# Adafruit_CCS811_STEMMA_QT.net
KiCad netlist of a schematic drawn in EAGLE
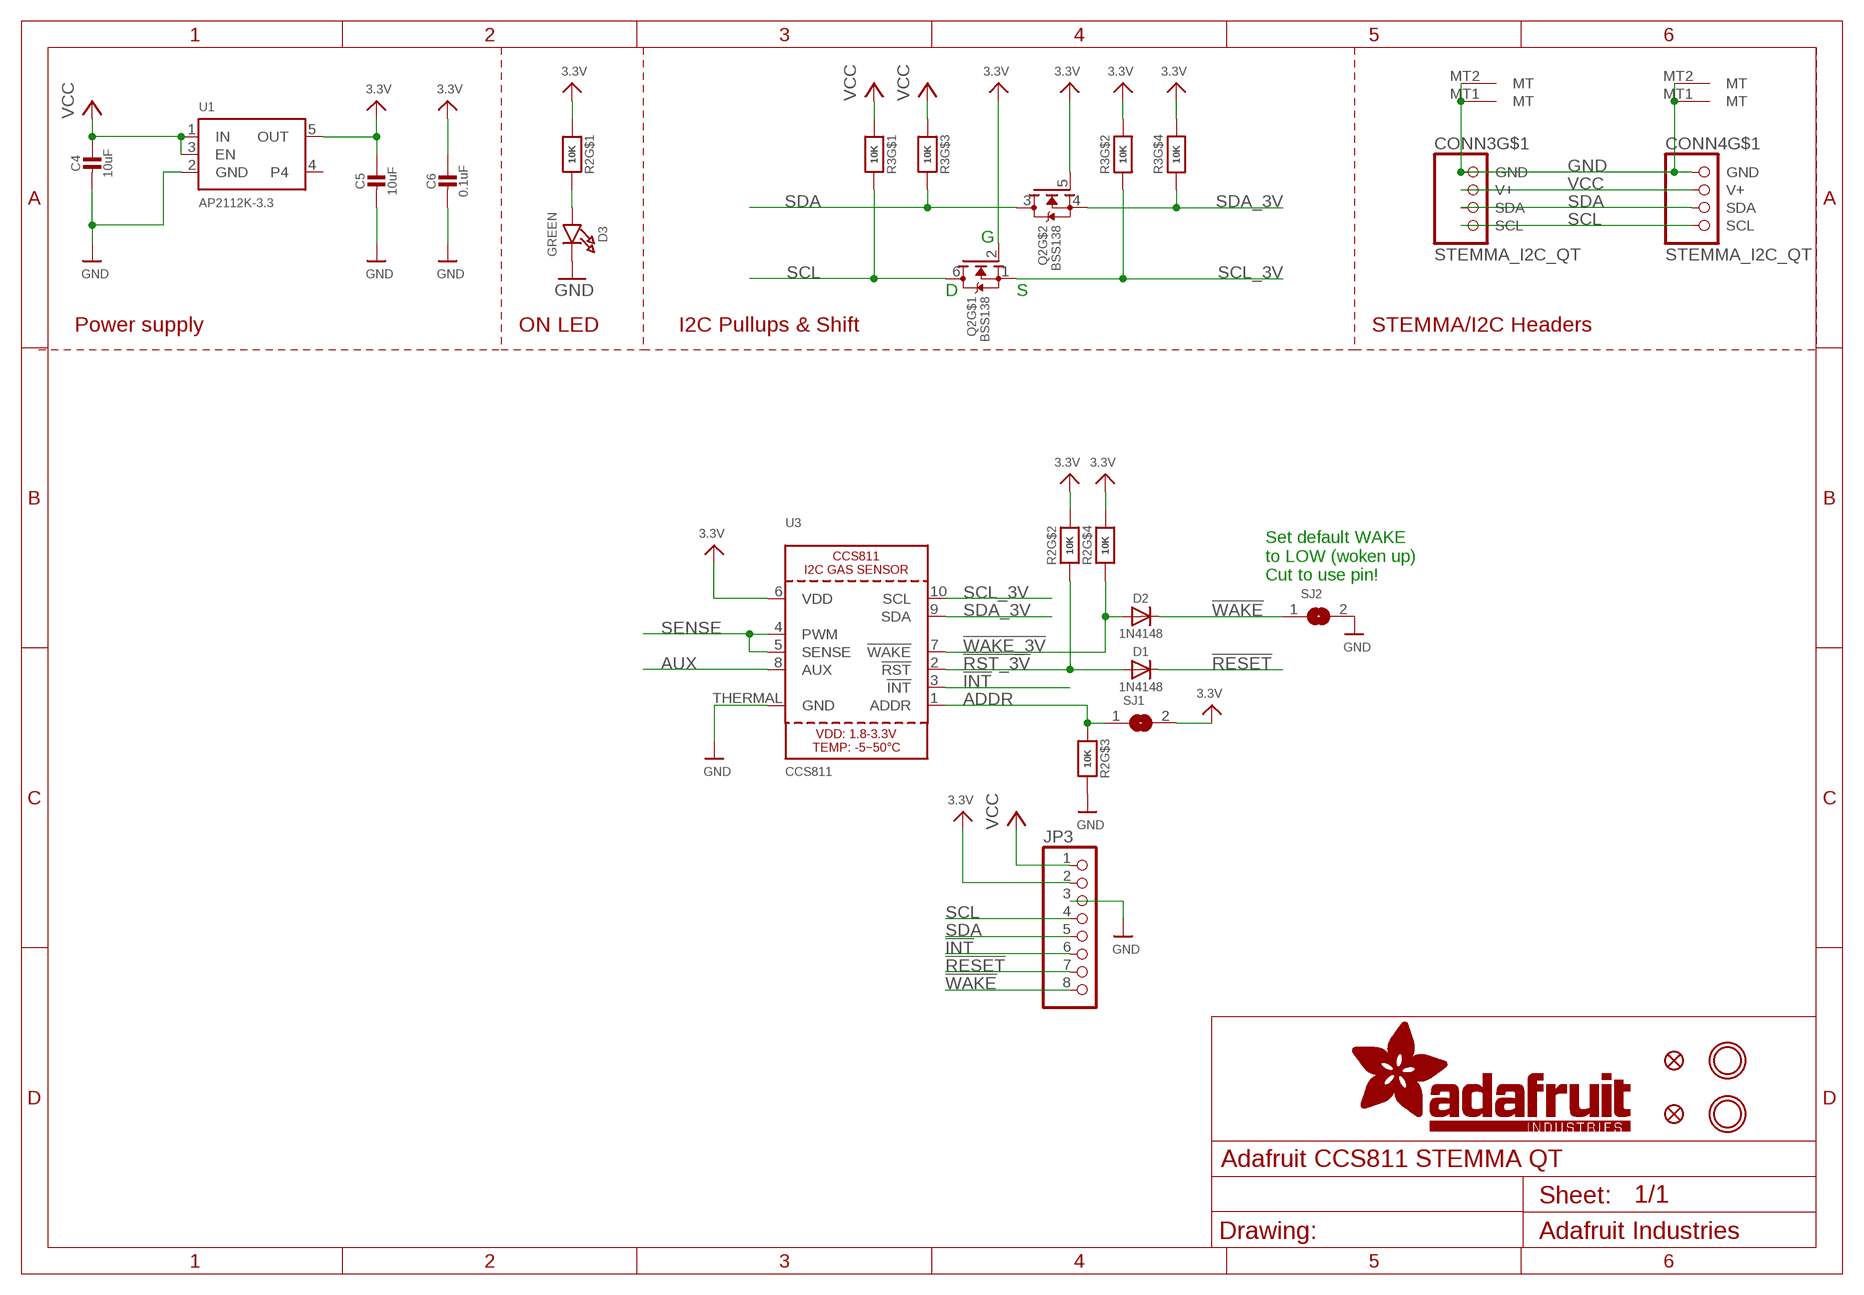
[diagram p0: schematic, sheet 1]

(export (version "E")
  (design (tool "Eeschema 10.0.6"))
  (components
    (comp (ref "C4")
      (value "10uF")
      (footprint "eagle-import:0805-NO")
      (libsource (lib "eagle-import") (part "CAP_CERAMIC0805-NOOUTLINE"))
    )
    (comp (ref "C5")
      (value "10uF")
      (footprint "eagle-import:0805-NO")
      (libsource (lib "eagle-import") (part "CAP_CERAMIC0805-NOOUTLINE"))
    )
    (comp (ref "C6")
      (value "0.1uF")
      (footprint "eagle-import:0603-NO")
      (libsource (lib "eagle-import") (part "CAP_CERAMIC0603_NO"))
    )
    (comp (ref "CONN3")
      (value "STEMMA_I2C_QT")
      (footprint "eagle-import:JST_SH4")
      (libsource (lib "eagle-import") (part "STEMMA_I2C_QT"))
    )
    (comp (ref "CONN4")
      (value "STEMMA_I2C_QT")
      (footprint "eagle-import:JST_SH4")
      (libsource (lib "eagle-import") (part "STEMMA_I2C_QT"))
    )
    (comp (ref "D1")
      (value "1N4148")
      (footprint "eagle-import:SOD-323")
      (libsource (lib "eagle-import") (part "DIODESOD-323"))
    )
    (comp (ref "D2")
      (value "1N4148")
      (footprint "eagle-import:SOD-323")
      (libsource (lib "eagle-import") (part "DIODESOD-323"))
    )
    (comp (ref "D3")
      (value "GREEN")
      (footprint "eagle-import:CHIPLED_0603_NOOUTLINE")
      (libsource (lib "eagle-import") (part "LED0603_NOOUTLINE"))
    )
    (comp (ref "FID3")
      (value "FIDUCIAL_1MM")
      (footprint "eagle-import:FIDUCIAL_1MM")
      (libsource (lib "eagle-import") (part "FIDUCIAL_1MM"))
    )
    (comp (ref "FID4")
      (value "FIDUCIAL_1MM")
      (footprint "eagle-import:FIDUCIAL_1MM")
      (libsource (lib "eagle-import") (part "FIDUCIAL_1MM"))
    )
    (comp (ref "JP3")
      (value "HEADER-1X870MIL")
      (footprint "eagle-import:1X08_ROUND_70")
      (libsource (lib "eagle-import") (part "HEADER-1X870MIL"))
    )
    (comp (ref "Q2")
      (value "BSS138")
      (footprint "eagle-import:SOT363")
      (libsource (lib "eagle-import") (part "MOSFET-N_DUAL"))
    )
    (comp (ref "R2")
      (value "10K")
      (footprint "eagle-import:RESPACK_4X0603")
      (libsource (lib "eagle-import") (part "RESISTOR_4PACK"))
    )
    (comp (ref "R3")
      (value "10K")
      (footprint "eagle-import:RESPACK_4X0603")
      (libsource (lib "eagle-import") (part "RESISTOR_4PACK"))
    )
    (comp (ref "SJ1")
      (value "SOLDERJUMPER")
      (footprint "eagle-import:SOLDERJUMPER_ARROW_NOPASTE")
      (libsource (lib "eagle-import") (part "SOLDERJUMPER"))
    )
    (comp (ref "SJ2")
      (value "SOLDERJUMPERCLOSED")
      (footprint "eagle-import:SOLDERJUMPER_CLOSEDWIRE")
      (libsource (lib "eagle-import") (part "SOLDERJUMPERCLOSED"))
    )
    (comp (ref "U$39")
      (value "MOUNTINGHOLE2.5")
      (footprint "eagle-import:MOUNTINGHOLE_2.5_PLATED")
      (libsource (lib "eagle-import") (part "MOUNTINGHOLE2.5"))
    )
    (comp (ref "U$40")
      (value "MOUNTINGHOLE2.5")
      (footprint "eagle-import:MOUNTINGHOLE_2.5_PLATED")
      (libsource (lib "eagle-import") (part "MOUNTINGHOLE2.5"))
    )
    (comp (ref "U1")
      (value "AP2112K-3.3")
      (footprint "eagle-import:SOT23-5")
      (libsource (lib "eagle-import") (part "VREG_SOT23-5"))
    )
    (comp (ref "U3")
      (value "CCS811")
      (footprint "eagle-import:CCS811")
      (libsource (lib "eagle-import") (part "CCS811"))
    )
  )
  (nets
    (net (code "1") (name "/ADDR") (class "Default")
      (node (ref "R2") (pin "3") (pinfunction "1_3") (pintype "passive"))
      (node (ref "SJ1") (pin "1") (pinfunction "1_1") (pintype "passive"))
      (node (ref "U3") (pin "1") (pinfunction "ADDR_1") (pintype "input"))
    )
    (net (code "2") (name "/AUX") (class "Default")
      (node (ref "U3") (pin "8") (pinfunction "AUX_8") (pintype "passive"))
    )
    (net (code "3") (name "/SCL") (class "Default")
      (node (ref "CONN3") (pin "4") (pinfunction "SCL_4") (pintype "passive"))
      (node (ref "CONN4") (pin "4") (pinfunction "SCL_4") (pintype "passive"))
      (node (ref "JP3") (pin "4") (pinfunction "4_4") (pintype "passive"))
      (node (ref "Q2") (pin "6") (pinfunction "D_6") (pintype "bidirectional"))
      (node (ref "R3") (pin "8") (pinfunction "2_8") (pintype "passive"))
    )
    (net (code "4") (name "/SCL_3V") (class "Default")
      (node (ref "Q2") (pin "1") (pinfunction "S_1") (pintype "bidirectional"))
      (node (ref "R3") (pin "7") (pinfunction "2_7") (pintype "passive"))
      (node (ref "U3") (pin "10") (pinfunction "SCL_10") (pintype "bidirectional"))
    )
    (net (code "5") (name "/SDA") (class "Default")
      (node (ref "CONN3") (pin "3") (pinfunction "SDA_3") (pintype "passive"))
      (node (ref "CONN4") (pin "3") (pinfunction "SDA_3") (pintype "passive"))
      (node (ref "JP3") (pin "5") (pinfunction "5_5") (pintype "passive"))
      (node (ref "Q2") (pin "3") (pinfunction "D_3") (pintype "bidirectional"))
      (node (ref "R3") (pin "6") (pinfunction "2_6") (pintype "passive"))
    )
    (net (code "6") (name "/SDA_3V") (class "Default")
      (node (ref "Q2") (pin "4") (pinfunction "S_4") (pintype "bidirectional"))
      (node (ref "R3") (pin "5") (pinfunction "2_5") (pintype "passive"))
      (node (ref "U3") (pin "9") (pinfunction "SDA_9") (pintype "bidirectional"))
    )
    (net (code "7") (name "/SENSE") (class "Default")
      (node (ref "U3") (pin "4") (pinfunction "PWM_4") (pintype "output"))
      (node (ref "U3") (pin "5") (pinfunction "SENSE_5") (pintype "input"))
    )
    (net (code "8") (name "/~{INT}") (class "Default")
      (node (ref "JP3") (pin "6") (pinfunction "6_6") (pintype "passive"))
      (node (ref "U3") (pin "3") (pinfunction "~{INT}_3") (pintype "output"))
    )
    (net (code "9") (name "/~{RESET}") (class "Default")
      (node (ref "D1") (pin "C") (pinfunction "C_C") (pintype "passive"))
      (node (ref "JP3") (pin "7") (pinfunction "7_7") (pintype "passive"))
    )
    (net (code "10") (name "/~{RST_3V}") (class "Default")
      (node (ref "D1") (pin "A") (pinfunction "A_A") (pintype "passive"))
      (node (ref "R2") (pin "2") (pinfunction "1_2") (pintype "passive"))
      (node (ref "U3") (pin "2") (pinfunction "~{RST}_2") (pintype "input"))
    )
    (net (code "11") (name "/~{WAKE_3V}") (class "Default")
      (node (ref "D2") (pin "A") (pinfunction "A_A") (pintype "passive"))
      (node (ref "R2") (pin "4") (pinfunction "1_4") (pintype "passive"))
      (node (ref "U3") (pin "7") (pinfunction "~{WAKE}_7") (pintype "input"))
    )
    (net (code "12") (name "/~{WAKE}") (class "Default")
      (node (ref "D2") (pin "C") (pinfunction "C_C") (pintype "passive"))
      (node (ref "JP3") (pin "8") (pinfunction "8_8") (pintype "passive"))
      (node (ref "SJ2") (pin "1") (pinfunction "1_1") (pintype "passive"))
    )
    (net (code "13") (name "3.3V") (class "Default")
      (node (ref "C5") (pin "1") (pinfunction "1_1") (pintype "passive"))
      (node (ref "C6") (pin "1") (pinfunction "1_1") (pintype "passive"))
      (node (ref "JP3") (pin "2") (pinfunction "2_2") (pintype "passive"))
      (node (ref "Q2") (pin "2") (pinfunction "G_2") (pintype "bidirectional"))
      (node (ref "Q2") (pin "5") (pinfunction "G_5") (pintype "bidirectional"))
      (node (ref "R2") (pin "1") (pinfunction "1_1") (pintype "passive"))
      (node (ref "R2") (pin "5") (pinfunction "2_5") (pintype "passive"))
      (node (ref "R2") (pin "7") (pinfunction "2_7") (pintype "passive"))
      (node (ref "R3") (pin "2") (pinfunction "1_2") (pintype "passive"))
      (node (ref "R3") (pin "4") (pinfunction "1_4") (pintype "passive"))
      (node (ref "SJ1") (pin "2") (pinfunction "2_2") (pintype "passive"))
      (node (ref "U1") (pin "5") (pinfunction "OUT_5") (pintype "power_in"))
      (node (ref "U3") (pin "6") (pinfunction "VDD_6") (pintype "power_in"))
    )
    (net (code "14") (name "GND") (class "Default")
      (node (ref "C4") (pin "2") (pinfunction "2_2") (pintype "passive"))
      (node (ref "C5") (pin "2") (pinfunction "2_2") (pintype "passive"))
      (node (ref "C6") (pin "2") (pinfunction "2_2") (pintype "passive"))
      (node (ref "CONN3") (pin "1") (pinfunction "GND_1") (pintype "passive"))
      (node (ref "CONN3") (pin "MT1") (pinfunction "MT_MT1") (pintype "bidirectional"))
      (node (ref "CONN3") (pin "MT2") (pinfunction "MT_MT2") (pintype "bidirectional"))
      (node (ref "CONN4") (pin "1") (pinfunction "GND_1") (pintype "passive"))
      (node (ref "CONN4") (pin "MT1") (pinfunction "MT_MT1") (pintype "bidirectional"))
      (node (ref "CONN4") (pin "MT2") (pinfunction "MT_MT2") (pintype "bidirectional"))
      (node (ref "D3") (pin "C") (pinfunction "C_C") (pintype "passive"))
      (node (ref "JP3") (pin "3") (pinfunction "3_3") (pintype "passive"))
      (node (ref "R2") (pin "6") (pinfunction "2_6") (pintype "passive"))
      (node (ref "SJ2") (pin "2") (pinfunction "2_2") (pintype "passive"))
      (node (ref "U1") (pin "2") (pinfunction "GND_2") (pintype "power_in"))
      (node (ref "U3") (pin "THERMAL") (pinfunction "GND_THERMAL") (pintype "power_in"))
    )
    (net (code "15") (name "Net-(R2A-2)") (class "Default")
      (node (ref "D3") (pin "A") (pinfunction "A_A") (pintype "passive"))
      (node (ref "R2") (pin "8") (pinfunction "2_8") (pintype "passive"))
    )
    (net (code "16") (name "VCC") (class "Default")
      (node (ref "C4") (pin "1") (pinfunction "1_1") (pintype "passive"))
      (node (ref "CONN3") (pin "2") (pinfunction "V+_2") (pintype "passive"))
      (node (ref "CONN4") (pin "2") (pinfunction "V+_2") (pintype "passive"))
      (node (ref "JP3") (pin "1") (pinfunction "1_1") (pintype "passive"))
      (node (ref "R3") (pin "1") (pinfunction "1_1") (pintype "passive"))
      (node (ref "R3") (pin "3") (pinfunction "1_3") (pintype "passive"))
      (node (ref "U1") (pin "1") (pinfunction "IN_1") (pintype "power_in"))
      (node (ref "U1") (pin "3") (pinfunction "EN_3") (pintype "input"))
    )
    (net (code "17") (name "unconnected-(U1-P4-Pad4)") (class "Default")
      (node (ref "U1") (pin "4") (pinfunction "P4_4") (pintype "bidirectional"))
    )
  )
)
